# ESP-RX.net
KiCad netlist of a schematic drawn in Altium Designer
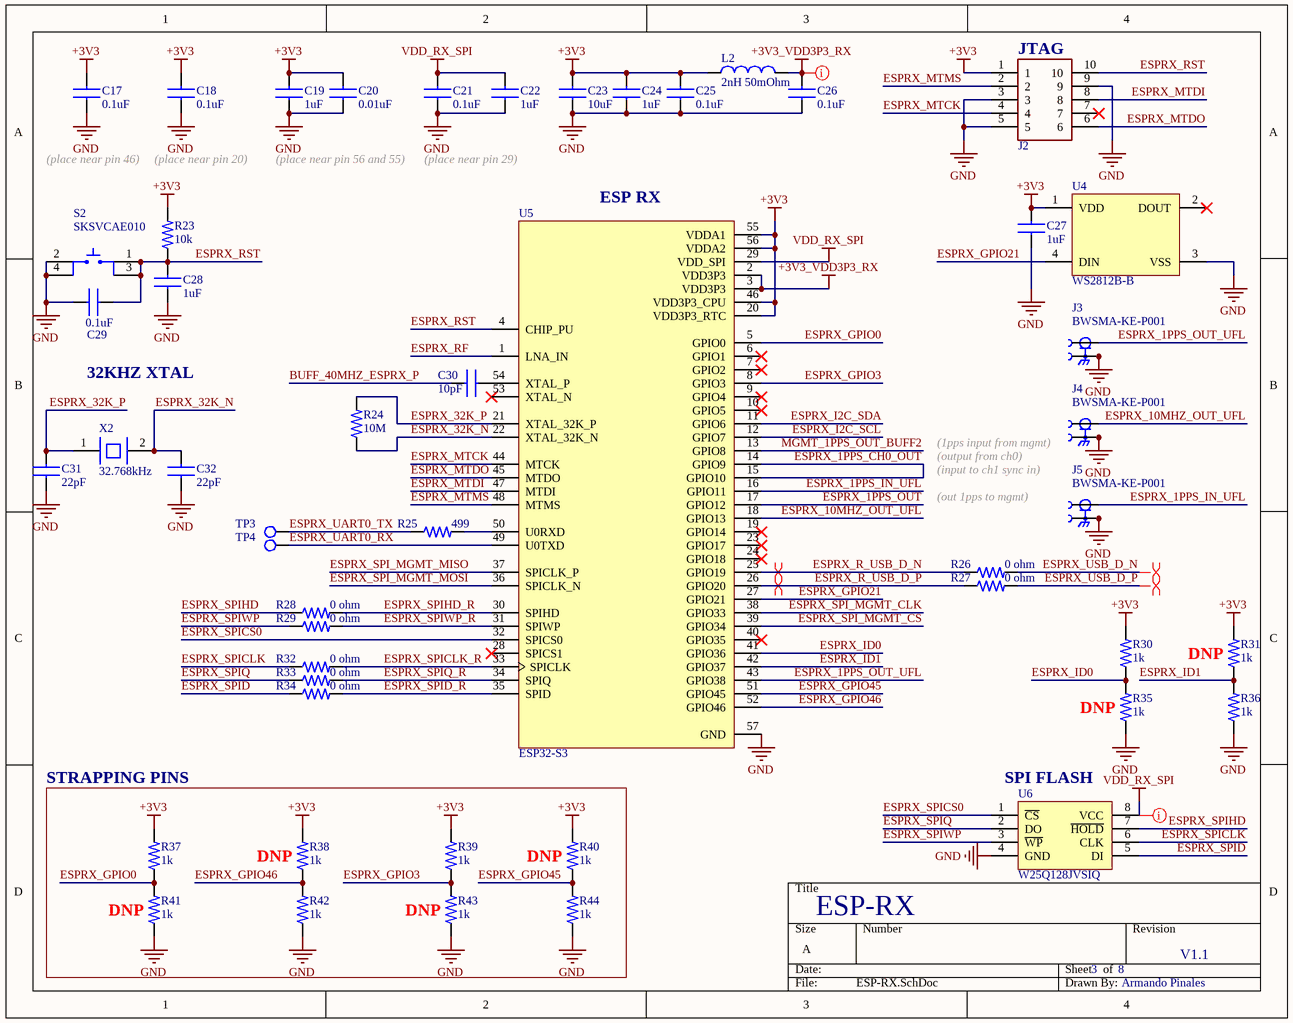
[diagram p0: ESP-RX.SchDoc]

(export (version "E")
  (design (tool "Eeschema 10.0.6"))
  (components
    (comp (ref "C17")
      (value "0.1uF")
      (footprint "CAP_0402")
      (description "Cap Ceramic 0.1uF 16V X7R 10% SMD 0402 125C Paper T/R")
      (fields
        (field (name "MANUFACTURER") "Murata")
        (field (name "MANUFACTURER PART NUMBER") "GCM155R71C104KA55J")
      )
      (libsource (lib "LotusSound") (part "CAP_GCM155R71C104KA55J"))
    )
    (comp (ref "C18")
      (value "0.1uF")
      (footprint "CAP_0402")
      (description "Cap Ceramic 0.1uF 16V X7R 10% SMD 0402 125C Paper T/R")
      (fields
        (field (name "MANUFACTURER") "Murata")
        (field (name "MANUFACTURER PART NUMBER") "GCM155R71C104KA55J")
      )
      (libsource (lib "LotusSound") (part "CAP_GCM155R71C104KA55J"))
    )
    (comp (ref "C19")
      (value "1uF")
      (footprint "CAP_0402")
      (description "Cap Ceramic 1uF 25V X5R 10% SMD 0402 85°C Cardboard T/R")
      (fields
        (field (name "MANUFACTURER") "Samsung")
        (field (name "MANUFACTURER PART NUMBER") "CL05A105KA5NQNC")
      )
      (libsource (lib "LotusSound") (part "CAP_CL05A105KA5NQNC"))
    )
    (comp (ref "C20")
      (value "0.01uF")
      (footprint "CAP_0402")
      (description "Cap Ceramic 0.01uF 50V X7R 10% Pad SMD 0402 125°C T/R")
      (fields
        (field (name "MANUFACTURER") "Yageo")
        (field (name "MANUFACTURER PART NUMBER") "CC0402KRX7R9BB103")
      )
      (libsource (lib "LotusSound") (part "CAP_CC0402KRX7R9BB103"))
    )
    (comp (ref "C21")
      (value "0.1uF")
      (footprint "CAP_0402")
      (description "Cap Ceramic 0.1uF 16V X7R 10% SMD 0402 125C Paper T/R")
      (fields
        (field (name "MANUFACTURER") "Murata")
        (field (name "MANUFACTURER PART NUMBER") "GCM155R71C104KA55J")
      )
      (libsource (lib "LotusSound") (part "CAP_GCM155R71C104KA55J"))
    )
    (comp (ref "C22")
      (value "1uF")
      (footprint "CAP_0402")
      (description "Cap Ceramic 1uF 25V X5R 10% SMD 0402 85°C Cardboard T/R")
      (fields
        (field (name "MANUFACTURER") "Samsung")
        (field (name "MANUFACTURER PART NUMBER") "CL05A105KA5NQNC")
      )
      (libsource (lib "LotusSound") (part "CAP_CL05A105KA5NQNC"))
    )
    (comp (ref "C23")
      (value "10uF")
      (footprint "CAP_0402")
      (description "Cap Ceramic 10uF 6.3V X5R 20% SMD 0402 85°C Paper T/R")
      (fields
        (field (name "MANUFACTURER") "Samsung")
        (field (name "MANUFACTURER PART NUMBER") "CL05A106MQ5NUNC")
      )
      (libsource (lib "LotusSound") (part "CAP_CL05A106MQ5NUNC"))
    )
    (comp (ref "C24")
      (value "1uF")
      (footprint "CAP_0402")
      (description "Cap Ceramic 1uF 25V X5R 10% SMD 0402 85°C Cardboard T/R")
      (fields
        (field (name "MANUFACTURER") "Samsung")
        (field (name "MANUFACTURER PART NUMBER") "CL05A105KA5NQNC")
      )
      (libsource (lib "LotusSound") (part "CAP_CL05A105KA5NQNC"))
    )
    (comp (ref "C25")
      (value "0.1uF")
      (footprint "CAP_0402")
      (description "Cap Ceramic 0.1uF 16V X7R 10% SMD 0402 125C Paper T/R")
      (fields
        (field (name "MANUFACTURER") "Murata")
        (field (name "MANUFACTURER PART NUMBER") "GCM155R71C104KA55J")
      )
      (libsource (lib "LotusSound") (part "CAP_GCM155R71C104KA55J"))
    )
    (comp (ref "C26")
      (value "0.1uF")
      (footprint "CAP_0402")
      (description "Cap Ceramic 0.1uF 16V X7R 10% SMD 0402 125C Paper T/R")
      (fields
        (field (name "MANUFACTURER") "Murata")
        (field (name "MANUFACTURER PART NUMBER") "GCM155R71C104KA55J")
      )
      (libsource (lib "LotusSound") (part "CAP_GCM155R71C104KA55J"))
    )
    (comp (ref "C27")
      (value "1uF")
      (footprint "CAP_0402")
      (description "Cap Ceramic 1uF 25V X5R 10% SMD 0402 85°C Cardboard T/R")
      (fields
        (field (name "MANUFACTURER") "Samsung")
        (field (name "MANUFACTURER PART NUMBER") "CL05A105KA5NQNC")
      )
      (libsource (lib "LotusSound") (part "CAP_CL05A105KA5NQNC"))
    )
    (comp (ref "C28")
      (value "1uF")
      (footprint "CAP_0402")
      (description "Cap Ceramic 1uF 25V X5R 10% SMD 0402 85°C Cardboard T/R")
      (fields
        (field (name "MANUFACTURER") "Samsung")
        (field (name "MANUFACTURER PART NUMBER") "CL05A105KA5NQNC")
      )
      (libsource (lib "LotusSound") (part "CAP_CL05A105KA5NQNC"))
    )
    (comp (ref "C29")
      (value "0.1uF")
      (footprint "CAP_0402")
      (description "Cap Ceramic 0.1uF 16V X7R 10% SMD 0402 125C Paper T/R")
      (fields
        (field (name "MANUFACTURER") "Murata")
        (field (name "MANUFACTURER PART NUMBER") "GCM155R71C104KA55J")
      )
      (libsource (lib "LotusSound") (part "CAP_GCM155R71C104KA55J"))
    )
    (comp (ref "C30")
      (value "10pF")
      (footprint "CAP_0402")
      (description "Cap Ceramic 10pF 50V C0G 0.5pF Pad SMD 0402 150C Automotive T/R")
      (fields
        (field (name "MANUFACTURER") "TDK")
        (field (name "MANUFACTURER PART NUMBER") "CGA2B2NP01H100D050BA")
      )
      (libsource (lib "LotusSound") (part "CAP_CGA2B2NP01H100D050BA"))
    )
    (comp (ref "C31")
      (value "22pF")
      (footprint "CAP_0402")
      (description "0402 22 pF 50 V ±5 % Tolerance NP0 SMT Multilayer Ceramic Capacitor")
      (fields
        (field (name "MANUFACTURER") "Yageo")
        (field (name "MANUFACTURER PART NUMBER") "CC0402JRNPO9BN220")
      )
      (libsource (lib "LotusSound") (part "CAP_CC0402JRNPO9BN220"))
    )
    (comp (ref "C32")
      (value "22pF")
      (footprint "CAP_0402")
      (description "0402 22 pF 50 V ±5 % Tolerance NP0 SMT Multilayer Ceramic Capacitor")
      (fields
        (field (name "MANUFACTURER") "Yageo")
        (field (name "MANUFACTURER PART NUMBER") "CC0402JRNPO9BN220")
      )
      (libsource (lib "LotusSound") (part "CAP_CC0402JRNPO9BN220"))
    )
    (comp (ref "J2")
      (value "CONN_TC2050-IDC")
      (footprint "CONN_TAG-CONNECT_TC2050-IDC")
      (description "Cbl Plug-Of-Nails 10-Pin w/Legs")
      (fields (field (name "MF") "{'manufacturer': u'Tag-Connect LLC'}") (field (name "MP") "TC2050-IDC"))
      (libsource (lib "LotusSound") (part "CONN_TC2050-IDC"))
    )
    (comp (ref "J3")
      (value "BWSMA-KE-P001")
      (footprint "CONN_BWSMA-KE-P001")
      (description "0-12.4GHz 50Ω 335V 直插偏脚")
      (fields (field (name "MANUFACTURER") "BAT Wireless"))
      (libsource (lib "LotusSound") (part "CONN_BWSMA-KE-P001"))
    )
    (comp (ref "J4")
      (value "BWSMA-KE-P001")
      (footprint "CONN_BWSMA-KE-P001")
      (description "0-12.4GHz 50Ω 335V 直插偏脚")
      (fields (field (name "MANUFACTURER") "BAT Wireless"))
      (libsource (lib "LotusSound") (part "CONN_BWSMA-KE-P001"))
    )
    (comp (ref "J5")
      (value "BWSMA-KE-P001")
      (footprint "CONN_BWSMA-KE-P001")
      (description "0-12.4GHz 50Ω 335V 直插偏脚")
      (fields (field (name "MANUFACTURER") "BAT Wireless"))
      (libsource (lib "LotusSound") (part "CONN_BWSMA-KE-P001"))
    )
    (comp (ref "L2")
      (value "2nH 50mOhm")
      (footprint "IND_INDC1006X60N")
      (description "FIXED IND 2NH 1A 50 MOHM SMD")
      (fields (field (name "MF") "{'manufacturer': u'TDK'}") (field (name "MP") "MHQ1005P2N0STD25"))
      (libsource (lib "LotusSound") (part "IND_MHQ1005P2N0STD25"))
    )
    (comp (ref "R23")
      (value "10k")
      (footprint "RES_0402")
      (description "RES SMD 10K OHM 1% 1/16W 0402")
      (fields
        (field (name "MANUFACTURER") "Yageo")
        (field (name "MANUFACTURER PART NUMBER") "AC0402FR-0710KL")
      )
      (libsource (lib "LotusSound") (part "RES_AC0402FR-0710KL"))
    )
    (comp (ref "R24")
      (value "10M")
      (footprint "RES_0402")
      (description "Res Thick Film 0402 10M Ohm 5% 0.063W(1/16W) ±100ppm/C Pad SMD Automotive T/R")
      (fields
        (field (name "MANUFACTURER") "TE Connectivity")
        (field (name "MANUFACTURER PART NUMBER") "CRGCQ0402J10M")
      )
      (libsource (lib "LotusSound") (part "RES_CRGCQ0402J10M"))
    )
    (comp (ref "R25")
      (value "499")
      (footprint "RES_0402")
      (description "Res General Purpose Thick Film 0402 499 Ohm 1% 1/16W ±100ppm/°C Molded SMD Paper T/R")
      (fields
        (field (name "MANUFACTURER") "Yageo")
        (field (name "MANUFACTURER PART NUMBER") "RC0402FR-07499RL")
      )
      (libsource (lib "LotusSound") (part "RES_RC0402FR-07499RL"))
    )
    (comp (ref "R26")
      (value "0 ohm")
      (footprint "RES_0402")
      (description "RES SMD 0 OHM JUMPER 1/16W 0402")
      (fields
        (field (name "MANUFACTURER") "Yageo")
        (field (name "MANUFACTURER PART NUMBER") "RC0402JR-070RL")
      )
      (libsource (lib "LotusSound") (part "RES_RC0402JR-070RL"))
    )
    (comp (ref "R27")
      (value "0 ohm")
      (footprint "RES_0402")
      (description "RES SMD 0 OHM JUMPER 1/16W 0402")
      (fields
        (field (name "MANUFACTURER") "Yageo")
        (field (name "MANUFACTURER PART NUMBER") "RC0402JR-070RL")
      )
      (libsource (lib "LotusSound") (part "RES_RC0402JR-070RL"))
    )
    (comp (ref "R28")
      (value "0 ohm")
      (footprint "RES_0402")
      (description "RES SMD 0 OHM JUMPER 1/16W 0402")
      (fields
        (field (name "MANUFACTURER") "Yageo")
        (field (name "MANUFACTURER PART NUMBER") "RC0402JR-070RL")
      )
      (libsource (lib "LotusSound") (part "RES_RC0402JR-070RL"))
    )
    (comp (ref "R29")
      (value "0 ohm")
      (footprint "RES_0402")
      (description "RES SMD 0 OHM JUMPER 1/16W 0402")
      (fields
        (field (name "MANUFACTURER") "Yageo")
        (field (name "MANUFACTURER PART NUMBER") "RC0402JR-070RL")
      )
      (libsource (lib "LotusSound") (part "RES_RC0402JR-070RL"))
    )
    (comp (ref "R30")
      (value "1k")
      (footprint "RES_0402")
      (description "Res General Purpose Thick Film 0402 1K Ohm 5% 1/16W ±100ppm/°C Molded SMD Paper T/R")
      (fields
        (field (name "MANUFACTURER") "Yageo")
        (field (name "MANUFACTURER PART NUMBER") "RC0402JR-071KL")
      )
      (libsource (lib "LotusSound") (part "RES_RC0402JR-071KL"))
    )
    (comp (ref "R31")
      (value "1k")
      (footprint "RES_0402")
      (description "Res General Purpose Thick Film 0402 1K Ohm 5% 1/16W ±100ppm/°C Molded SMD Paper T/R")
      (fields
        (field (name "MANUFACTURER") "Yageo")
        (field (name "MANUFACTURER PART NUMBER") "RC0402JR-071KL")
      )
      (libsource (lib "LotusSound") (part "RES_RC0402JR-071KL"))
    )
    (comp (ref "R32")
      (value "0 ohm")
      (footprint "RES_0402")
      (description "RES SMD 0 OHM JUMPER 1/16W 0402")
      (fields
        (field (name "MANUFACTURER") "Yageo")
        (field (name "MANUFACTURER PART NUMBER") "RC0402JR-070RL")
      )
      (libsource (lib "LotusSound") (part "RES_RC0402JR-070RL"))
    )
    (comp (ref "R33")
      (value "0 ohm")
      (footprint "RES_0402")
      (description "RES SMD 0 OHM JUMPER 1/16W 0402")
      (fields
        (field (name "MANUFACTURER") "Yageo")
        (field (name "MANUFACTURER PART NUMBER") "RC0402JR-070RL")
      )
      (libsource (lib "LotusSound") (part "RES_RC0402JR-070RL"))
    )
    (comp (ref "R34")
      (value "0 ohm")
      (footprint "RES_0402")
      (description "RES SMD 0 OHM JUMPER 1/16W 0402")
      (fields
        (field (name "MANUFACTURER") "Yageo")
        (field (name "MANUFACTURER PART NUMBER") "RC0402JR-070RL")
      )
      (libsource (lib "LotusSound") (part "RES_RC0402JR-070RL"))
    )
    (comp (ref "R35")
      (value "1k")
      (footprint "RES_0402")
      (description "Res General Purpose Thick Film 0402 1K Ohm 5% 1/16W ±100ppm/°C Molded SMD Paper T/R")
      (fields
        (field (name "MANUFACTURER") "Yageo")
        (field (name "MANUFACTURER PART NUMBER") "RC0402JR-071KL")
      )
      (libsource (lib "LotusSound") (part "RES_RC0402JR-071KL"))
    )
    (comp (ref "R36")
      (value "1k")
      (footprint "RES_0402")
      (description "Res General Purpose Thick Film 0402 1K Ohm 5% 1/16W ±100ppm/°C Molded SMD Paper T/R")
      (fields
        (field (name "MANUFACTURER") "Yageo")
        (field (name "MANUFACTURER PART NUMBER") "RC0402JR-071KL")
      )
      (libsource (lib "LotusSound") (part "RES_RC0402JR-071KL"))
    )
    (comp (ref "R37")
      (value "1k")
      (footprint "RES_0402")
      (description "Res General Purpose Thick Film 0402 1K Ohm 5% 1/16W ±100ppm/°C Molded SMD Paper T/R")
      (fields
        (field (name "MANUFACTURER") "Yageo")
        (field (name "MANUFACTURER PART NUMBER") "RC0402JR-071KL")
      )
      (libsource (lib "LotusSound") (part "RES_RC0402JR-071KL"))
    )
    (comp (ref "R38")
      (value "1k")
      (footprint "RES_0402")
      (description "Res General Purpose Thick Film 0402 1K Ohm 5% 1/16W ±100ppm/°C Molded SMD Paper T/R")
      (fields
        (field (name "MANUFACTURER") "Yageo")
        (field (name "MANUFACTURER PART NUMBER") "RC0402JR-071KL")
      )
      (libsource (lib "LotusSound") (part "RES_RC0402JR-071KL"))
    )
    (comp (ref "R39")
      (value "1k")
      (footprint "RES_0402")
      (description "Res General Purpose Thick Film 0402 1K Ohm 5% 1/16W ±100ppm/°C Molded SMD Paper T/R")
      (fields
        (field (name "MANUFACTURER") "Yageo")
        (field (name "MANUFACTURER PART NUMBER") "RC0402JR-071KL")
      )
      (libsource (lib "LotusSound") (part "RES_RC0402JR-071KL"))
    )
    (comp (ref "R40")
      (value "1k")
      (footprint "RES_0402")
      (description "Res General Purpose Thick Film 0402 1K Ohm 5% 1/16W ±100ppm/°C Molded SMD Paper T/R")
      (fields
        (field (name "MANUFACTURER") "Yageo")
        (field (name "MANUFACTURER PART NUMBER") "RC0402JR-071KL")
      )
      (libsource (lib "LotusSound") (part "RES_RC0402JR-071KL"))
    )
    (comp (ref "R41")
      (value "1k")
      (footprint "RES_0402")
      (description "Res General Purpose Thick Film 0402 1K Ohm 5% 1/16W ±100ppm/°C Molded SMD Paper T/R")
      (fields
        (field (name "MANUFACTURER") "Yageo")
        (field (name "MANUFACTURER PART NUMBER") "RC0402JR-071KL")
      )
      (libsource (lib "LotusSound") (part "RES_RC0402JR-071KL"))
    )
    (comp (ref "R42")
      (value "1k")
      (footprint "RES_0402")
      (description "Res General Purpose Thick Film 0402 1K Ohm 5% 1/16W ±100ppm/°C Molded SMD Paper T/R")
      (fields
        (field (name "MANUFACTURER") "Yageo")
        (field (name "MANUFACTURER PART NUMBER") "RC0402JR-071KL")
      )
      (libsource (lib "LotusSound") (part "RES_RC0402JR-071KL"))
    )
    (comp (ref "R43")
      (value "1k")
      (footprint "RES_0402")
      (description "Res General Purpose Thick Film 0402 1K Ohm 5% 1/16W ±100ppm/°C Molded SMD Paper T/R")
      (fields
        (field (name "MANUFACTURER") "Yageo")
        (field (name "MANUFACTURER PART NUMBER") "RC0402JR-071KL")
      )
      (libsource (lib "LotusSound") (part "RES_RC0402JR-071KL"))
    )
    (comp (ref "R44")
      (value "1k")
      (footprint "RES_0402")
      (description "Res General Purpose Thick Film 0402 1K Ohm 5% 1/16W ±100ppm/°C Molded SMD Paper T/R")
      (fields
        (field (name "MANUFACTURER") "Yageo")
        (field (name "MANUFACTURER PART NUMBER") "RC0402JR-071KL")
      )
      (libsource (lib "LotusSound") (part "RES_RC0402JR-071KL"))
    )
    (comp (ref "S2")
      (value "SKSVCAE010")
      (footprint "SW_SKSVCAE010")
      (description "2.8x1.9mm Compact Type with Projection Surface Mount SKSV Series Tact Switch")
      (fields (field (name "MANUFACTURER") "Alps Electric"))
      (libsource (lib "LotusSound") (part "SW_SKSVCAE010"))
    )
    (comp (ref "TP3")
      (value "Test Point 1MM")
      (footprint "TP_PAD-1MM")
      (libsource (lib "LotusSound") (part "TP_PAD-1MM"))
    )
    (comp (ref "TP4")
      (value "Test Point 1MM")
      (footprint "TP_PAD-1MM")
      (libsource (lib "LotusSound") (part "TP_PAD-1MM"))
    )
    (comp (ref "U4")
      (value "WS2812B-B")
      (footprint "LED_WS2812B-B")
      (description "Intelligent control LED integrated light source")
      (fields
        (field (name "MANUFACTURER") "WORLDSEMI")
        (field (name "MANUFACTURER PART NUMBER") "WS2812B-B/W")
      )
      (libsource (lib "LotusSound") (part "LED_WS2812B-B"))
    )
    (comp (ref "U5")
      (value "ESP32-S3")
      (footprint "IC_ESP32-S3")
      (fields (field (name "MF") "Espressif Systems"))
      (libsource (lib "LotusSound") (part "IC_ESP32-S3"))
    )
    (comp (ref "U6")
      (value "W25Q128JVSIQ")
      (footprint "IC_W25Q128JVSIQ")
      (description "NOR Flash Serial (SPI, Dual SPI, Quad SPI) 3.3V 128M-bit 16M x 8 6ns 8-Pin SOIC Tube")
      (fields (field (name "MANUFACTURER") "Winbond"))
      (libsource (lib "LotusSound") (part "IC_W25Q128JVSIQ"))
    )
    (comp (ref "X2")
      (value "32.768kHz")
      (footprint "XTAL_X321532768KGD2SI")
      (description "贴片无源晶振 32.768KHZ 12.5PF ±20ppm –40~+85 ℃")
      (fields
        (field (name "MANUFACTURER") "YXC")
        (field (name "MANUFACTURER PART NUMBER") "X321532768KGD2SI")
      )
      (libsource (lib "LotusSound") (part "XTAL_X321532768KGD2SI"))
    )
  )
  (nets
    (net (code "1") (name "+3V3") (class "Default")
      (node (ref "C17") (pin "2") (pinfunction "2_2") (pintype "passive"))
      (node (ref "C18") (pin "2") (pinfunction "2_2") (pintype "passive"))
      (node (ref "C19") (pin "2") (pinfunction "2_2") (pintype "passive"))
      (node (ref "C20") (pin "2") (pinfunction "2_2") (pintype "passive"))
      (node (ref "C23") (pin "2") (pinfunction "2_2") (pintype "passive"))
      (node (ref "C24") (pin "2") (pinfunction "2_2") (pintype "passive"))
      (node (ref "C25") (pin "2") (pinfunction "2_2") (pintype "passive"))
      (node (ref "C27") (pin "2") (pinfunction "2_2") (pintype "passive"))
      (node (ref "J2") (pin "1") (pinfunction "1_1") (pintype "passive"))
      (node (ref "L2") (pin "1") (pinfunction "1_1") (pintype "passive"))
      (node (ref "R23") (pin "2") (pinfunction "2_2") (pintype "passive"))
      (node (ref "R30") (pin "2") (pinfunction "2_2") (pintype "passive"))
      (node (ref "R31") (pin "2") (pinfunction "2_2") (pintype "passive"))
      (node (ref "R37") (pin "2") (pinfunction "2_2") (pintype "passive"))
      (node (ref "R38") (pin "2") (pinfunction "2_2") (pintype "passive"))
      (node (ref "R39") (pin "2") (pinfunction "2_2") (pintype "passive"))
      (node (ref "R40") (pin "2") (pinfunction "2_2") (pintype "passive"))
      (node (ref "U4") (pin "1") (pinfunction "VDD_1") (pintype "power_in"))
      (node (ref "U5") (pin "20") (pinfunction "VDD3P3_RTC_20") (pintype "passive"))
      (node (ref "U5") (pin "46") (pinfunction "VDD3P3_CPU_46") (pintype "passive"))
      (node (ref "U5") (pin "55") (pinfunction "VDDA1_55") (pintype "power_in"))
      (node (ref "U5") (pin "56") (pinfunction "VDDA2_56") (pintype "passive"))
    )
    (net (code "2") (name "+3V3_VDD3P3_RX") (class "Default")
      (node (ref "C26") (pin "2") (pinfunction "2_2") (pintype "passive"))
      (node (ref "L2") (pin "2") (pinfunction "2_2") (pintype "passive"))
      (node (ref "U5") (pin "2") (pinfunction "VDD3P3_2") (pintype "passive"))
      (node (ref "U5") (pin "3") (pinfunction "VDD3P3_3") (pintype "passive"))
    )
    (net (code "3") (name "/BUFF_40MHZ_ESPRX_P") (class "Default")
      (node (ref "C30") (pin "1") (pinfunction "1_1") (pintype "passive"))
    )
    (net (code "4") (name "/ESPRX_1PPS_CH0_OUT") (class "Default")
      (node (ref "U5") (pin "14") (pinfunction "GPIO9_14") (pintype "passive"))
      (node (ref "U5") (pin "15") (pinfunction "GPIO10_15") (pintype "passive"))
    )
    (net (code "5") (name "/ESPRX_1PPS_IN_UFL") (class "Default")
      (node (ref "J5") (pin "1") (pinfunction "1_1") (pintype "passive"))
      (node (ref "U5") (pin "16") (pinfunction "GPIO11_16") (pintype "passive"))
    )
    (net (code "6") (name "/ESPRX_1PPS_OUT") (class "Default")
      (node (ref "U5") (pin "17") (pinfunction "GPIO12_17") (pintype "passive"))
    )
    (net (code "7") (name "/ESPRX_1PPS_OUT_UFL") (class "Default")
      (node (ref "J3") (pin "1") (pinfunction "1_1") (pintype "passive"))
      (node (ref "U5") (pin "43") (pinfunction "GPIO38_43") (pintype "passive"))
    )
    (net (code "8") (name "/ESPRX_10MHZ_OUT_UFL") (class "Default")
      (node (ref "J4") (pin "1") (pinfunction "1_1") (pintype "passive"))
      (node (ref "U5") (pin "18") (pinfunction "GPIO13_18") (pintype "passive"))
    )
    (net (code "9") (name "/ESPRX_32K_N") (class "Default")
      (node (ref "C32") (pin "2") (pinfunction "2_2") (pintype "passive"))
      (node (ref "R24") (pin "1") (pinfunction "1_1") (pintype "passive"))
      (node (ref "U5") (pin "22") (pinfunction "XTAL_32K_N_22") (pintype "passive"))
      (node (ref "X2") (pin "2") (pinfunction "GND_2") (pintype "power_in"))
    )
    (net (code "10") (name "/ESPRX_32K_P") (class "Default")
      (node (ref "C31") (pin "2") (pinfunction "2_2") (pintype "passive"))
      (node (ref "R24") (pin "2") (pinfunction "2_2") (pintype "passive"))
      (node (ref "U5") (pin "21") (pinfunction "XTAL_32K_P_21") (pintype "passive"))
      (node (ref "X2") (pin "1") (pinfunction "IN/OUT_1") (pintype "passive"))
    )
    (net (code "11") (name "/ESPRX_GPIO0") (class "Default")
      (node (ref "R37") (pin "1") (pinfunction "1_1") (pintype "passive"))
      (node (ref "R41") (pin "2") (pinfunction "2_2") (pintype "passive"))
      (node (ref "U5") (pin "5") (pinfunction "GPIO0_5") (pintype "passive"))
    )
    (net (code "12") (name "/ESPRX_GPIO3") (class "Default")
      (node (ref "R39") (pin "1") (pinfunction "1_1") (pintype "passive"))
      (node (ref "R43") (pin "2") (pinfunction "2_2") (pintype "passive"))
      (node (ref "U5") (pin "8") (pinfunction "GPIO3_8") (pintype "passive"))
    )
    (net (code "13") (name "/ESPRX_GPIO21") (class "Default")
      (node (ref "U4") (pin "4") (pinfunction "DIN_4") (pintype "passive"))
      (node (ref "U5") (pin "27") (pinfunction "GPIO21_27") (pintype "passive"))
    )
    (net (code "14") (name "/ESPRX_GPIO45") (class "Default")
      (node (ref "R40") (pin "1") (pinfunction "1_1") (pintype "passive"))
      (node (ref "R44") (pin "2") (pinfunction "2_2") (pintype "passive"))
      (node (ref "U5") (pin "51") (pinfunction "GPIO45_51") (pintype "passive"))
    )
    (net (code "15") (name "/ESPRX_GPIO46") (class "Default")
      (node (ref "R38") (pin "1") (pinfunction "1_1") (pintype "passive"))
      (node (ref "R42") (pin "2") (pinfunction "2_2") (pintype "passive"))
      (node (ref "U5") (pin "52") (pinfunction "GPIO46_52") (pintype "passive"))
    )
    (net (code "16") (name "/ESPRX_I2C_SCL") (class "Default")
      (node (ref "U5") (pin "12") (pinfunction "GPIO7_12") (pintype "passive"))
    )
    (net (code "17") (name "/ESPRX_I2C_SDA") (class "Default")
      (node (ref "U5") (pin "11") (pinfunction "GPIO6_11") (pintype "passive"))
    )
    (net (code "18") (name "/ESPRX_ID0") (class "Default")
      (node (ref "R30") (pin "1") (pinfunction "1_1") (pintype "passive"))
      (node (ref "R35") (pin "2") (pinfunction "2_2") (pintype "passive"))
      (node (ref "U5") (pin "41") (pinfunction "GPIO36_41") (pintype "passive"))
    )
    (net (code "19") (name "/ESPRX_ID1") (class "Default")
      (node (ref "R31") (pin "1") (pinfunction "1_1") (pintype "passive"))
      (node (ref "R36") (pin "2") (pinfunction "2_2") (pintype "passive"))
      (node (ref "U5") (pin "42") (pinfunction "GPIO37_42") (pintype "passive"))
    )
    (net (code "20") (name "/ESPRX_MTCK") (class "Default")
      (node (ref "J2") (pin "4") (pinfunction "4_4") (pintype "passive"))
      (node (ref "U5") (pin "44") (pinfunction "MTCK_44") (pintype "passive"))
    )
    (net (code "21") (name "/ESPRX_MTDI") (class "Default")
      (node (ref "J2") (pin "8") (pinfunction "8_8") (pintype "passive"))
      (node (ref "U5") (pin "47") (pinfunction "MTDI_47") (pintype "passive"))
    )
    (net (code "22") (name "/ESPRX_MTDO") (class "Default")
      (node (ref "J2") (pin "6") (pinfunction "6_6") (pintype "passive"))
      (node (ref "U5") (pin "45") (pinfunction "MTDO_45") (pintype "passive"))
    )
    (net (code "23") (name "/ESPRX_MTMS") (class "Default")
      (node (ref "J2") (pin "2") (pinfunction "2_2") (pintype "passive"))
      (node (ref "U5") (pin "48") (pinfunction "MTMS_48") (pintype "passive"))
    )
    (net (code "24") (name "/ESPRX_RF") (class "Default")
      (node (ref "U5") (pin "1") (pinfunction "LNA_IN_1") (pintype "passive"))
    )
    (net (code "25") (name "/ESPRX_RST") (class "Default")
      (node (ref "C28") (pin "2") (pinfunction "2_2") (pintype "passive"))
      (node (ref "C29") (pin "2") (pinfunction "2_2") (pintype "passive"))
      (node (ref "J2") (pin "10") (pinfunction "10_10") (pintype "passive"))
      (node (ref "R23") (pin "1") (pinfunction "1_1") (pintype "passive"))
      (node (ref "S2") (pin "1") (pinfunction "1_1") (pintype "passive"))
      (node (ref "S2") (pin "3") (pinfunction "3_3") (pintype "passive"))
      (node (ref "U5") (pin "4") (pinfunction "CHIP_PU_4") (pintype "passive"))
    )
    (net (code "26") (name "/ESPRX_R_USB_D_N") (class "Default")
      (node (ref "R26") (pin "1") (pinfunction "1_1") (pintype "passive"))
      (node (ref "U5") (pin "25") (pinfunction "GPIO19_25") (pintype "passive"))
    )
    (net (code "27") (name "/ESPRX_R_USB_D_P") (class "Default")
      (node (ref "R27") (pin "1") (pinfunction "1_1") (pintype "passive"))
      (node (ref "U5") (pin "26") (pinfunction "GPIO20_26") (pintype "passive"))
    )
    (net (code "28") (name "/ESPRX_SPICLK") (class "Default")
      (node (ref "R32") (pin "1") (pinfunction "1_1") (pintype "passive"))
      (node (ref "U6") (pin "6") (pinfunction "CLK_6") (pintype "passive"))
    )
    (net (code "29") (name "/ESPRX_SPICLK_R") (class "Default")
      (node (ref "R32") (pin "2") (pinfunction "2_2") (pintype "passive"))
      (node (ref "U5") (pin "33") (pinfunction "SPICLK_33") (pintype "passive"))
    )
    (net (code "30") (name "/ESPRX_SPICS0") (class "Default")
      (node (ref "U5") (pin "32") (pinfunction "SPICS0_32") (pintype "passive"))
      (node (ref "U6") (pin "1") (pinfunction "~{CS}_1") (pintype "passive"))
    )
    (net (code "31") (name "/ESPRX_SPID") (class "Default")
      (node (ref "R34") (pin "1") (pinfunction "1_1") (pintype "passive"))
      (node (ref "U6") (pin "5") (pinfunction "DI_5") (pintype "passive"))
    )
    (net (code "32") (name "/ESPRX_SPID_R") (class "Default")
      (node (ref "R34") (pin "2") (pinfunction "2_2") (pintype "passive"))
      (node (ref "U5") (pin "35") (pinfunction "SPID_35") (pintype "passive"))
    )
    (net (code "33") (name "/ESPRX_SPIHD") (class "Default")
      (node (ref "R28") (pin "1") (pinfunction "1_1") (pintype "passive"))
      (node (ref "U6") (pin "7") (pinfunction "~{HOLD}_7") (pintype "passive"))
    )
    (net (code "34") (name "/ESPRX_SPIHD_R") (class "Default")
      (node (ref "R28") (pin "2") (pinfunction "2_2") (pintype "passive"))
      (node (ref "U5") (pin "30") (pinfunction "SPIHD_30") (pintype "passive"))
    )
    (net (code "35") (name "/ESPRX_SPIQ") (class "Default")
      (node (ref "R33") (pin "1") (pinfunction "1_1") (pintype "passive"))
      (node (ref "U6") (pin "2") (pinfunction "DO_2") (pintype "passive"))
    )
    (net (code "36") (name "/ESPRX_SPIQ_R") (class "Default")
      (node (ref "R33") (pin "2") (pinfunction "2_2") (pintype "passive"))
      (node (ref "U5") (pin "34") (pinfunction "SPIQ_34") (pintype "passive"))
    )
    (net (code "37") (name "/ESPRX_SPIWP") (class "Default")
      (node (ref "R29") (pin "1") (pinfunction "1_1") (pintype "passive"))
      (node (ref "U6") (pin "3") (pinfunction "~{WP}_3") (pintype "passive"))
    )
    (net (code "38") (name "/ESPRX_SPIWP_R") (class "Default")
      (node (ref "R29") (pin "2") (pinfunction "2_2") (pintype "passive"))
      (node (ref "U5") (pin "31") (pinfunction "SPIWP_31") (pintype "passive"))
    )
    (net (code "39") (name "/ESPRX_SPI_MGMT_CLK") (class "Default")
      (node (ref "U5") (pin "38") (pinfunction "GPIO33_38") (pintype "passive"))
    )
    (net (code "40") (name "/ESPRX_SPI_MGMT_CS") (class "Default")
      (node (ref "U5") (pin "39") (pinfunction "GPIO34_39") (pintype "passive"))
    )
    (net (code "41") (name "/ESPRX_SPI_MGMT_MISO") (class "Default")
      (node (ref "U5") (pin "37") (pinfunction "SPICLK_P_37") (pintype "passive"))
    )
    (net (code "42") (name "/ESPRX_SPI_MGMT_MOSI") (class "Default")
      (node (ref "U5") (pin "36") (pinfunction "SPICLK_N_36") (pintype "passive"))
    )
    (net (code "43") (name "/ESPRX_UART0_RX") (class "Default")
      (node (ref "TP4") (pin "1") (pinfunction "1_1") (pintype "passive"))
      (node (ref "U5") (pin "49") (pinfunction "U0TXD_49") (pintype "passive"))
    )
    (net (code "44") (name "/ESPRX_UART0_TX") (class "Default")
      (node (ref "R25") (pin "1") (pinfunction "1_1") (pintype "passive"))
      (node (ref "TP3") (pin "1") (pinfunction "1_1") (pintype "passive"))
    )
    (net (code "45") (name "/ESPRX_USB_D_N") (class "Default")
      (node (ref "R26") (pin "2") (pinfunction "2_2") (pintype "passive"))
    )
    (net (code "46") (name "/ESPRX_USB_D_P") (class "Default")
      (node (ref "R27") (pin "2") (pinfunction "2_2") (pintype "passive"))
    )
    (net (code "47") (name "/MGMT_1PPS_OUT_BUFF2") (class "Default")
      (node (ref "U5") (pin "13") (pinfunction "GPIO8_13") (pintype "passive"))
    )
    (net (code "48") (name "GND") (class "Default")
      (node (ref "C17") (pin "1") (pinfunction "1_1") (pintype "passive"))
      (node (ref "C18") (pin "1") (pinfunction "1_1") (pintype "passive"))
      (node (ref "C19") (pin "1") (pinfunction "1_1") (pintype "passive"))
      (node (ref "C20") (pin "1") (pinfunction "1_1") (pintype "passive"))
      (node (ref "C21") (pin "1") (pinfunction "1_1") (pintype "passive"))
      (node (ref "C22") (pin "1") (pinfunction "1_1") (pintype "passive"))
      (node (ref "C23") (pin "1") (pinfunction "1_1") (pintype "passive"))
      (node (ref "C24") (pin "1") (pinfunction "1_1") (pintype "passive"))
      (node (ref "C25") (pin "1") (pinfunction "1_1") (pintype "passive"))
      (node (ref "C26") (pin "1") (pinfunction "1_1") (pintype "passive"))
      (node (ref "C27") (pin "1") (pinfunction "1_1") (pintype "passive"))
      (node (ref "C28") (pin "1") (pinfunction "1_1") (pintype "passive"))
      (node (ref "C29") (pin "1") (pinfunction "1_1") (pintype "passive"))
      (node (ref "C31") (pin "1") (pinfunction "1_1") (pintype "passive"))
      (node (ref "C32") (pin "1") (pinfunction "1_1") (pintype "passive"))
      (node (ref "J2") (pin "3") (pinfunction "3_3") (pintype "passive"))
      (node (ref "J2") (pin "5") (pinfunction "5_5") (pintype "passive"))
      (node (ref "J2") (pin "9") (pinfunction "9_9") (pintype "passive"))
      (node (ref "J3") (pin "2") (pinfunction "2_2") (pintype "passive"))
      (node (ref "J3") (pin "3") (pinfunction "3_3") (pintype "passive"))
      (node (ref "J3") (pin "4") (pinfunction "4_4") (pintype "passive"))
      (node (ref "J3") (pin "5") (pinfunction "5_5") (pintype "passive"))
      (node (ref "J4") (pin "2") (pinfunction "2_2") (pintype "passive"))
      (node (ref "J4") (pin "3") (pinfunction "3_3") (pintype "passive"))
      (node (ref "J4") (pin "4") (pinfunction "4_4") (pintype "passive"))
      (node (ref "J4") (pin "5") (pinfunction "5_5") (pintype "passive"))
      (node (ref "J5") (pin "2") (pinfunction "2_2") (pintype "passive"))
      (node (ref "J5") (pin "3") (pinfunction "3_3") (pintype "passive"))
      (node (ref "J5") (pin "4") (pinfunction "4_4") (pintype "passive"))
      (node (ref "J5") (pin "5") (pinfunction "5_5") (pintype "passive"))
      (node (ref "R35") (pin "1") (pinfunction "1_1") (pintype "passive"))
      (node (ref "R36") (pin "1") (pinfunction "1_1") (pintype "passive"))
      (node (ref "R41") (pin "1") (pinfunction "1_1") (pintype "passive"))
      (node (ref "R42") (pin "1") (pinfunction "1_1") (pintype "passive"))
      (node (ref "R43") (pin "1") (pinfunction "1_1") (pintype "passive"))
      (node (ref "R44") (pin "1") (pinfunction "1_1") (pintype "passive"))
      (node (ref "S2") (pin "2") (pinfunction "2_2") (pintype "passive"))
      (node (ref "S2") (pin "4") (pinfunction "4_4") (pintype "passive"))
      (node (ref "U4") (pin "3") (pinfunction "VSS_3") (pintype "power_in"))
      (node (ref "U5") (pin "57") (pinfunction "GND_57") (pintype "passive"))
      (node (ref "U6") (pin "4") (pinfunction "GND_4") (pintype "power_in"))
    )
    (net (code "49") (name "Net-(U5-U0RXD)") (class "Default")
      (node (ref "R25") (pin "2") (pinfunction "2_2") (pintype "passive"))
      (node (ref "U5") (pin "50") (pinfunction "U0RXD_50") (pintype "passive"))
    )
    (net (code "50") (name "Net-(U5-XTAL_P)") (class "Default")
      (node (ref "C30") (pin "2") (pinfunction "2_2") (pintype "passive"))
      (node (ref "U5") (pin "54") (pinfunction "XTAL_P_54") (pintype "passive"))
    )
    (net (code "51") (name "VDD_RX_SPI") (class "Default")
      (node (ref "C21") (pin "2") (pinfunction "2_2") (pintype "passive"))
      (node (ref "C22") (pin "2") (pinfunction "2_2") (pintype "passive"))
      (node (ref "U5") (pin "29") (pinfunction "VDD_SPI_29") (pintype "passive"))
      (node (ref "U6") (pin "8") (pinfunction "VCC_8") (pintype "passive"))
    )
    (net (code "52") (name "unconnected-(J2-Pad7)") (class "Default")
      (node (ref "J2") (pin "7") (pinfunction "7_7") (pintype "passive+no_connect"))
    )
    (net (code "53") (name "unconnected-(U4-DOUT-Pad2)") (class "Default")
      (node (ref "U4") (pin "2") (pinfunction "DOUT_2") (pintype "passive+no_connect"))
    )
    (net (code "54") (name "unconnected-(U5-GPIO1-Pad6)") (class "Default")
      (node (ref "U5") (pin "6") (pinfunction "GPIO1_6") (pintype "passive+no_connect"))
    )
    (net (code "55") (name "unconnected-(U5-GPIO2-Pad7)") (class "Default")
      (node (ref "U5") (pin "7") (pinfunction "GPIO2_7") (pintype "passive+no_connect"))
    )
    (net (code "56") (name "unconnected-(U5-GPIO4-Pad9)") (class "Default")
      (node (ref "U5") (pin "9") (pinfunction "GPIO4_9") (pintype "passive+no_connect"))
    )
    (net (code "57") (name "unconnected-(U5-GPIO5-Pad10)") (class "Default")
      (node (ref "U5") (pin "10") (pinfunction "GPIO5_10") (pintype "passive+no_connect"))
    )
    (net (code "58") (name "unconnected-(U5-GPIO14-Pad19)") (class "Default")
      (node (ref "U5") (pin "19") (pinfunction "GPIO14_19") (pintype "passive+no_connect"))
    )
    (net (code "59") (name "unconnected-(U5-GPIO17-Pad23)") (class "Default")
      (node (ref "U5") (pin "23") (pinfunction "GPIO17_23") (pintype "passive+no_connect"))
    )
    (net (code "60") (name "unconnected-(U5-GPIO18-Pad24)") (class "Default")
      (node (ref "U5") (pin "24") (pinfunction "GPIO18_24") (pintype "passive+no_connect"))
    )
    (net (code "61") (name "unconnected-(U5-GPIO35-Pad40)") (class "Default")
      (node (ref "U5") (pin "40") (pinfunction "GPIO35_40") (pintype "passive+no_connect"))
    )
    (net (code "62") (name "unconnected-(U5-SPICS1-Pad28)") (class "Default")
      (node (ref "U5") (pin "28") (pinfunction "SPICS1_28") (pintype "passive+no_connect"))
    )
    (net (code "63") (name "unconnected-(U5-XTAL_N-Pad53)") (class "Default")
      (node (ref "U5") (pin "53") (pinfunction "XTAL_N_53") (pintype "passive+no_connect"))
    )
  )
)
